# 1-Schematic_MicroCubeSat_B.net
KiCad netlist of a schematic drawn in EasyEDA
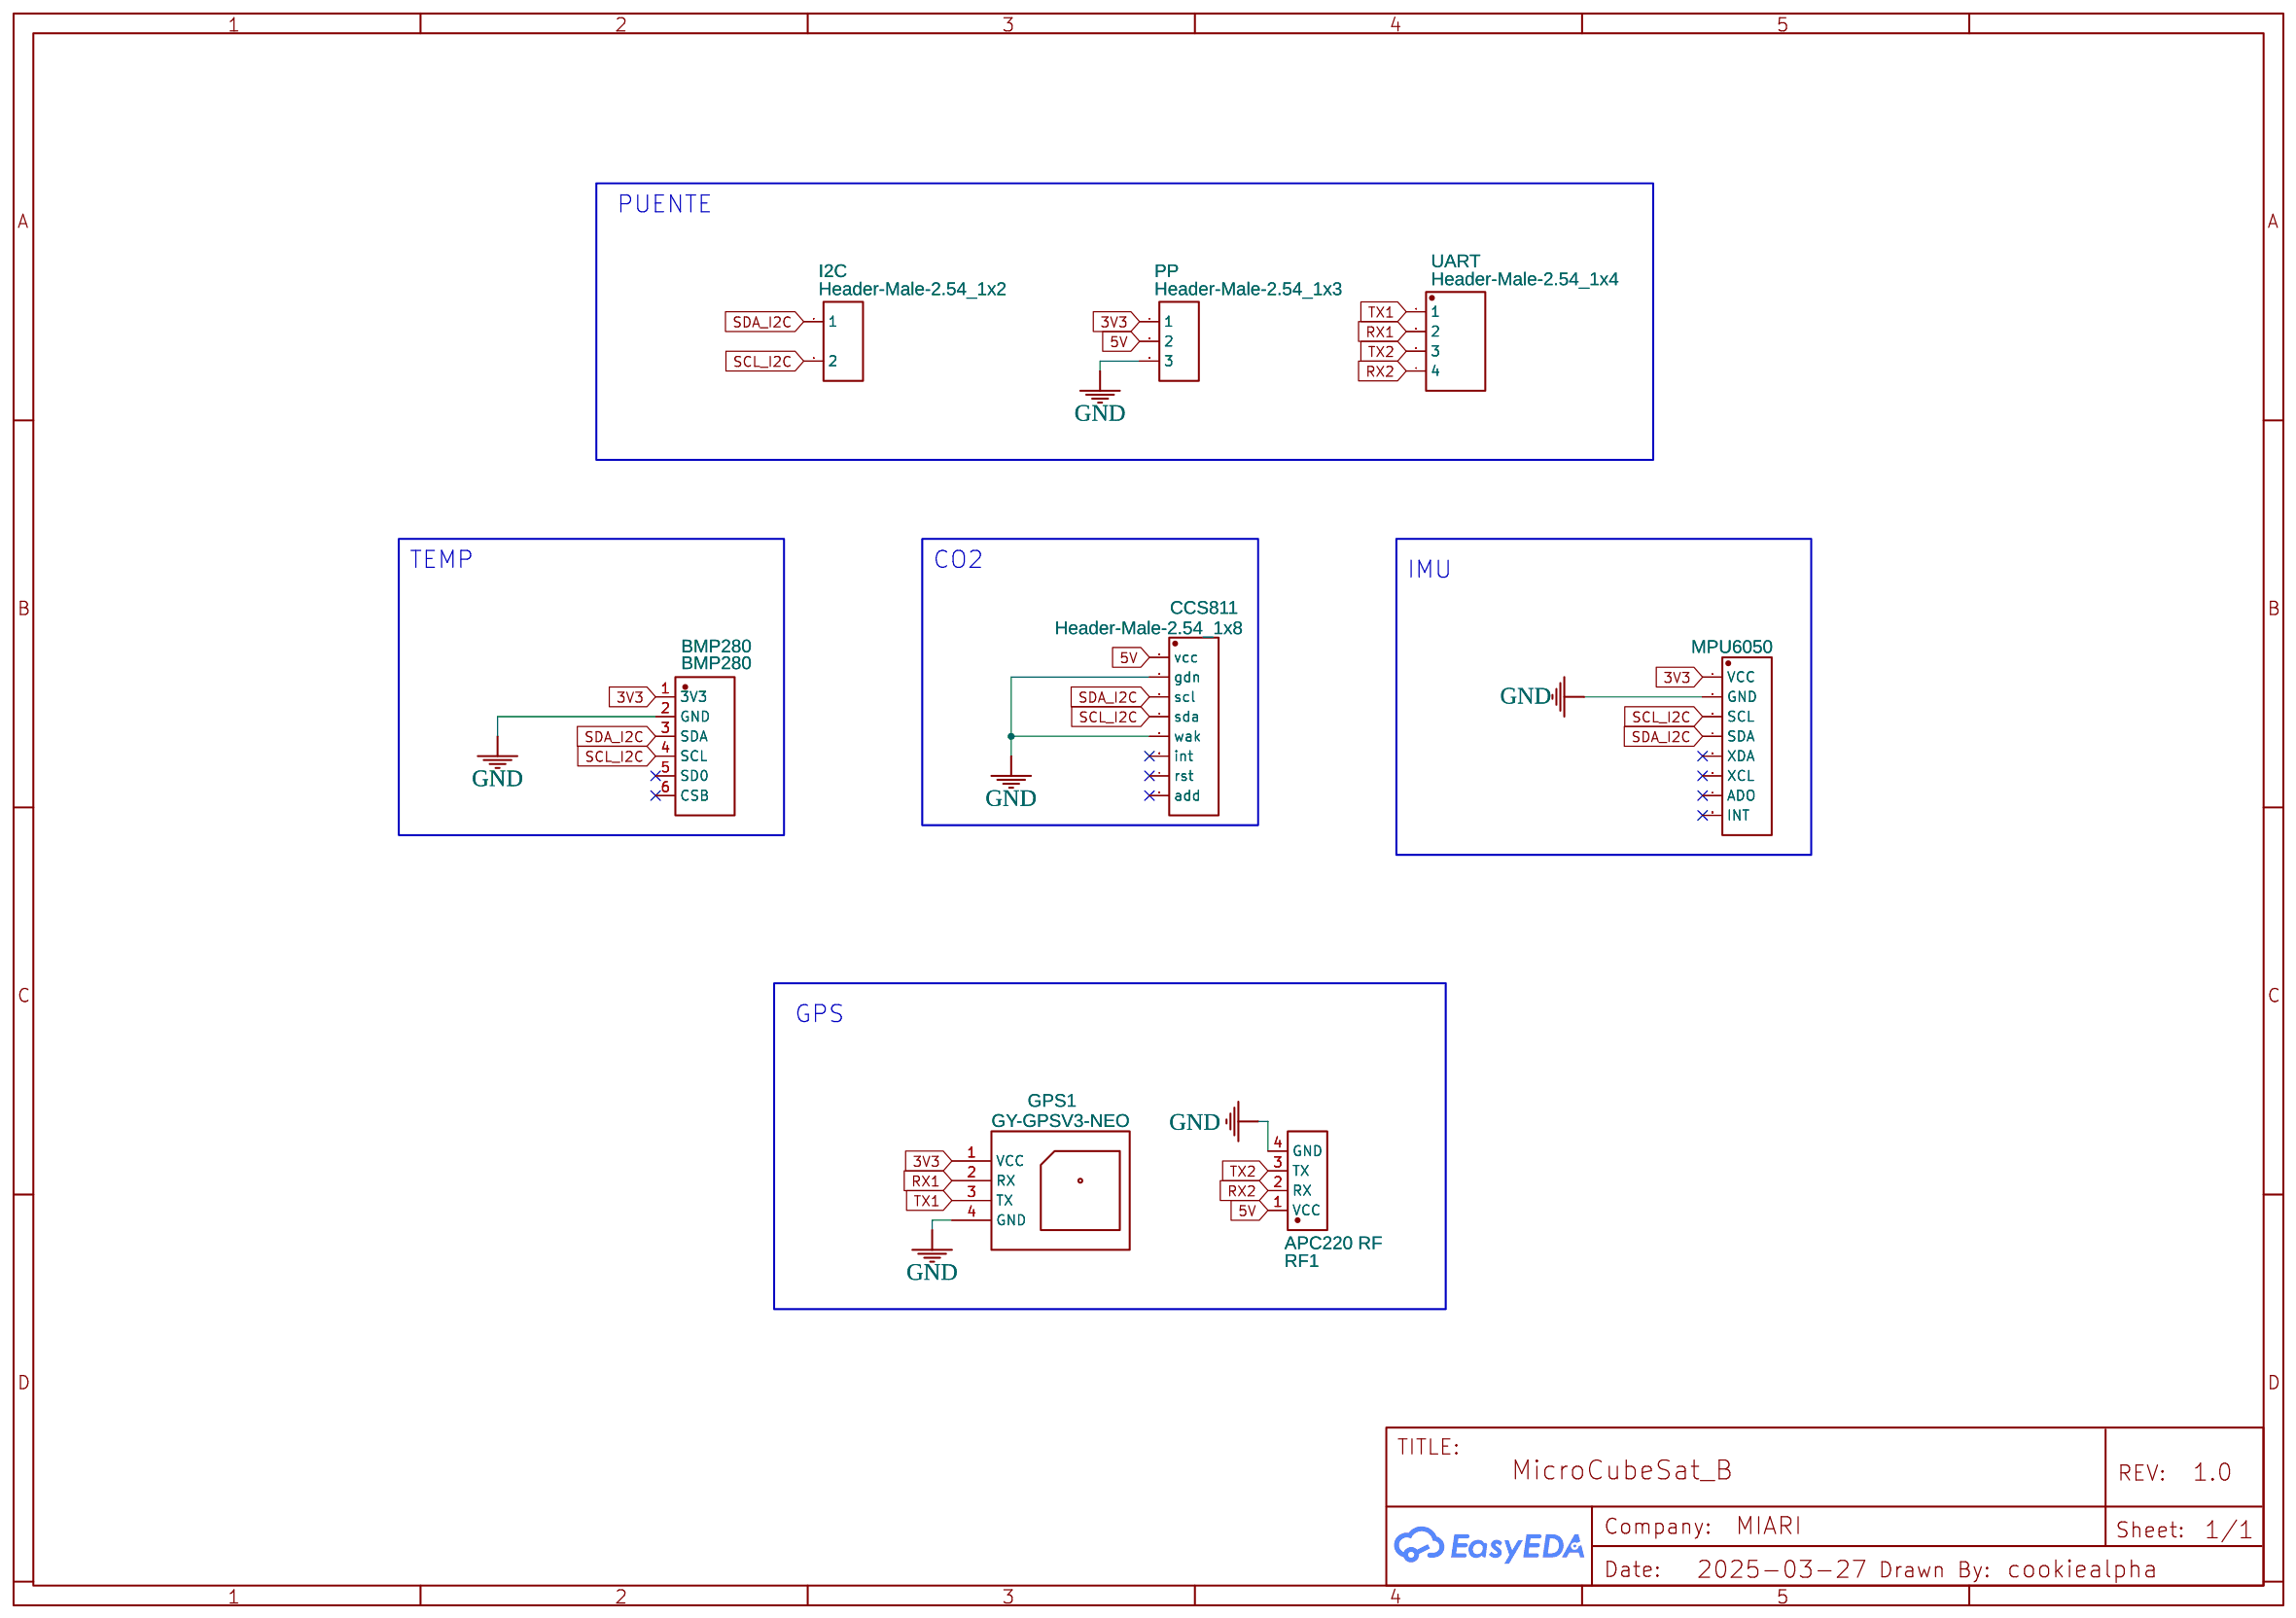
[diagram p0: schematic sheet]

(export (version "E")
  (design (tool "Eeschema 10.0.6"))
  (components
    (comp (ref "BMP280") (value "BMP280") (libsource (lib "") (part "BMP280_C9900132626")))
    (comp (ref "CCS811")
      (value "Header-Male-2.54_1x8")
      (fields (field (name "Manufacturer Part") "B-2100S08P-A110") (field (name "Manufacturer") "Ckmtw(灿科盟)"))
      (libsource (lib "") (part "Header-Male-2.54_1x8_1"))
    )
    (comp (ref "GPS1") (value "GY-GPSV3-NEO") (libsource (lib "") (part "GY-GPSV3-NEO")))
    (comp (ref "I2C")
      (value "Header-Male-2.54_1x2")
      (fields
        (field (name "Manufacturer Part") "826629-2")
        (field (name "Manufacturer") "TE Connectivity(泰科电子)")
      )
      (libsource (lib "") (part "Header-Male-2.54_1x2"))
    )
    (comp (ref "IMU1")
      (value "MPU6050")
      (fields (field (name "Manufacturer Part") "B-2100S08P-A110") (field (name "Manufacturer") "Ckmtw(灿科盟)"))
      (libsource (lib "") (part "Header-Male-2.54_1x8"))
    )
    (comp (ref "PP")
      (value "Header-Male-2.54_1x3")
      (fields (field (name "Manufacturer Part") "2.54-1*3P针") (field (name "Manufacturer") "BOOMELE(博穆精密)"))
      (libsource (lib "") (part "Header-Male-2.54_1x3"))
    )
    (comp (ref "RF1")
      (value "APC220 RF")
      (fields (field (name "Manufacturer Part") "HEADER_1*4P"))
      (libsource (lib "") (part "HEADER_1*4P"))
    )
    (comp (ref "UART")
      (value "Header-Male-2.54_1x4")
      (fields (field (name "Manufacturer Part") "B-2100S04P-A110") (field (name "Manufacturer") "Ckmtw(灿科盟)"))
      (libsource (lib "") (part "Header-Male-2.54_1x4"))
    )
  )
  (nets
    (net (code "1") (name "3V3") (class "Default")
      (node (ref "BMP280") (pin "1") (pinfunction "3V3_1") (pintype "unspecified"))
      (node (ref "GPS1") (pin "1") (pinfunction "VCC_1") (pintype "unspecified"))
      (node (ref "IMU1") (pin "1") (pinfunction "VCC_1") (pintype "unspecified"))
      (node (ref "PP") (pin "1") (pinfunction "1_1") (pintype "input"))
    )
    (net (code "2") (name "5V") (class "Default")
      (node (ref "CCS811") (pin "1") (pinfunction "vcc_1") (pintype "unspecified"))
      (node (ref "PP") (pin "2") (pinfunction "2_2") (pintype "input"))
      (node (ref "RF1") (pin "1") (pinfunction "VCC_1") (pintype "unspecified"))
    )
    (net (code "3") (name "GND") (class "Default")
      (node (ref "BMP280") (pin "2") (pinfunction "GND_2") (pintype "unspecified"))
      (node (ref "CCS811") (pin "2") (pinfunction "gdn_2") (pintype "unspecified"))
      (node (ref "CCS811") (pin "5") (pinfunction "wak_5") (pintype "unspecified"))
      (node (ref "GPS1") (pin "4") (pinfunction "GND_4") (pintype "unspecified"))
      (node (ref "IMU1") (pin "2") (pinfunction "GND_2") (pintype "unspecified"))
      (node (ref "PP") (pin "3") (pinfunction "3_3") (pintype "input"))
      (node (ref "RF1") (pin "4") (pinfunction "GND_4") (pintype "unspecified"))
    )
    (net (code "4") (name "RX1") (class "Default")
      (node (ref "GPS1") (pin "2") (pinfunction "RX_2") (pintype "unspecified"))
      (node (ref "UART") (pin "2") (pinfunction "2_2") (pintype "unspecified"))
    )
    (net (code "5") (name "RX2") (class "Default")
      (node (ref "RF1") (pin "2") (pinfunction "RX_2") (pintype "unspecified"))
      (node (ref "UART") (pin "4") (pinfunction "4_4") (pintype "unspecified"))
    )
    (net (code "6") (name "SCL_I2C") (class "Default")
      (node (ref "BMP280") (pin "4") (pinfunction "SCL_4") (pintype "unspecified"))
      (node (ref "CCS811") (pin "4") (pinfunction "sda_4") (pintype "unspecified"))
      (node (ref "I2C") (pin "2") (pinfunction "2_2") (pintype "unspecified"))
      (node (ref "IMU1") (pin "3") (pinfunction "SCL_3") (pintype "unspecified"))
    )
    (net (code "7") (name "SDA_I2C") (class "Default")
      (node (ref "BMP280") (pin "3") (pinfunction "SDA_3") (pintype "unspecified"))
      (node (ref "CCS811") (pin "3") (pinfunction "scl_3") (pintype "unspecified"))
      (node (ref "I2C") (pin "1") (pinfunction "1_1") (pintype "unspecified"))
      (node (ref "IMU1") (pin "4") (pinfunction "SDA_4") (pintype "unspecified"))
    )
    (net (code "8") (name "TX1") (class "Default")
      (node (ref "GPS1") (pin "3") (pinfunction "TX_3") (pintype "unspecified"))
      (node (ref "UART") (pin "1") (pinfunction "1_1") (pintype "unspecified"))
    )
    (net (code "9") (name "TX2") (class "Default")
      (node (ref "RF1") (pin "3") (pinfunction "TX_3") (pintype "unspecified"))
      (node (ref "UART") (pin "3") (pinfunction "3_3") (pintype "unspecified"))
    )
    (net (code "10") (name "unconnected-(BMP280-CSB-Pad6)") (class "Default")
      (node (ref "BMP280") (pin "6") (pinfunction "CSB_6") (pintype "unspecified+no_connect"))
    )
    (net (code "11") (name "unconnected-(BMP280-SD0-Pad5)") (class "Default")
      (node (ref "BMP280") (pin "5") (pinfunction "SD0_5") (pintype "unspecified+no_connect"))
    )
    (net (code "12") (name "unconnected-(CCS811-add-Pad8)") (class "Default")
      (node (ref "CCS811") (pin "8") (pinfunction "add_8") (pintype "unspecified+no_connect"))
    )
    (net (code "13") (name "unconnected-(CCS811-int-Pad6)") (class "Default")
      (node (ref "CCS811") (pin "6") (pinfunction "int_6") (pintype "unspecified+no_connect"))
    )
    (net (code "14") (name "unconnected-(CCS811-rst-Pad7)") (class "Default")
      (node (ref "CCS811") (pin "7") (pinfunction "rst_7") (pintype "unspecified+no_connect"))
    )
    (net (code "15") (name "unconnected-(IMU1-ADO-Pad7)") (class "Default")
      (node (ref "IMU1") (pin "7") (pinfunction "ADO_7") (pintype "unspecified+no_connect"))
    )
    (net (code "16") (name "unconnected-(IMU1-INT-Pad8)") (class "Default")
      (node (ref "IMU1") (pin "8") (pinfunction "INT_8") (pintype "unspecified+no_connect"))
    )
    (net (code "17") (name "unconnected-(IMU1-XCL-Pad6)") (class "Default")
      (node (ref "IMU1") (pin "6") (pinfunction "XCL_6") (pintype "unspecified+no_connect"))
    )
    (net (code "18") (name "unconnected-(IMU1-XDA-Pad5)") (class "Default")
      (node (ref "IMU1") (pin "5") (pinfunction "XDA_5") (pintype "unspecified+no_connect"))
    )
  )
)
